# battery_board.net
KiCad netlist of a schematic drawn in EAGLE
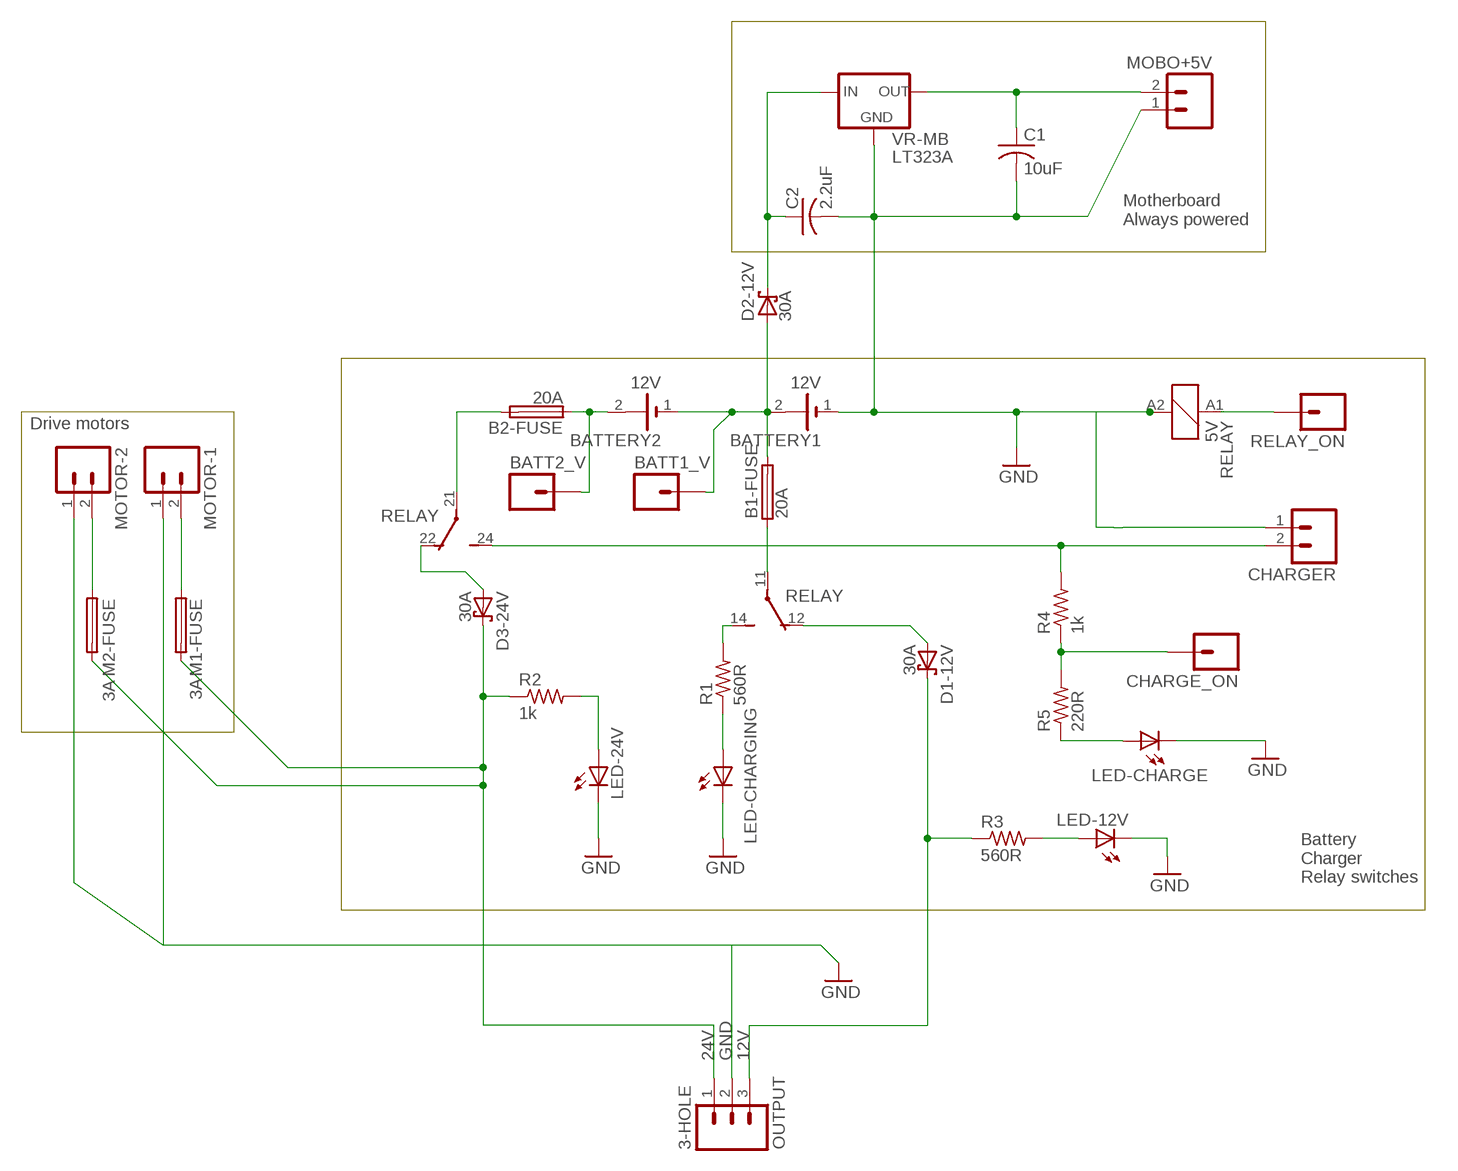
[diagram p0: schematic, sheet 1]

(export (version "E")
  (design (tool "Eeschema 10.0.6"))
  (components
    (comp (ref "B1-FUSE")
      (value "20A")
      (footprint "eagle-import:FUSE_BLADE")
      (libsource (lib "eagle-import") (part "FUSEBLADE"))
    )
    (comp (ref "B2-FUSE")
      (value "20A")
      (footprint "eagle-import:FUSE_BLADE")
      (libsource (lib "eagle-import") (part "FUSEBLADE"))
    )
    (comp (ref "BATT1_V")
      (value "1-HOLE")
      (footprint "eagle-import:1-HOLE_BIG")
      (libsource (lib "eagle-import") (part "1-HOLE"))
    )
    (comp (ref "BATT2_V")
      (value "1-HOLE")
      (footprint "eagle-import:1-HOLE_BIG")
      (libsource (lib "eagle-import") (part "1-HOLE"))
    )
    (comp (ref "BATTERY1")
      (value "12V")
      (footprint "eagle-import:SCREWTERMINAL-5MM-2")
      (libsource (lib "eagle-import") (part "BATTERY-ST"))
    )
    (comp (ref "BATTERY2")
      (value "12V")
      (footprint "eagle-import:SCREWTERMINAL-5MM-2")
      (libsource (lib "eagle-import") (part "BATTERY-ST"))
    )
    (comp (ref "C1")
      (value "10uF")
      (footprint "eagle-import:C050-024X044")
      (libsource (lib "eagle-import") (part "CAPACITOR"))
    )
    (comp (ref "C2")
      (value "2.2uF")
      (footprint "eagle-import:C050-024X044")
      (libsource (lib "eagle-import") (part "CAPACITOR"))
    )
    (comp (ref "CHARGER")
      (value "24V")
      (footprint "eagle-import:SCREWTERMINAL-5MM-2")
      (libsource (lib "eagle-import") (part "2-HOLESSC5MM"))
    )
    (comp (ref "CHARGE_ON")
      (value "1-HOLE")
      (footprint "eagle-import:1-HOLE_BIG")
      (libsource (lib "eagle-import") (part "1-HOLE"))
    )
    (comp (ref "D1-12V")
      (value "30A")
      (footprint "eagle-import:TO22-DIODE-H")
      (libsource (lib "eagle-import") (part "NTST30100SG-H"))
    )
    (comp (ref "D2-12V")
      (value "30A")
      (footprint "eagle-import:TO22-DIODE-H")
      (libsource (lib "eagle-import") (part "NTST30100SG-H"))
    )
    (comp (ref "D3-24V")
      (value "30A")
      (footprint "eagle-import:TO22-DIODE-H")
      (libsource (lib "eagle-import") (part "NTST30100SG-H"))
    )
    (comp (ref "LED-12V")
      (value "LED-5MM")
      (footprint "eagle-import:LED5MM")
      (libsource (lib "eagle-import") (part "LED-5MM"))
    )
    (comp (ref "LED-24V")
      (value "LED-5MM")
      (footprint "eagle-import:LED5MM")
      (libsource (lib "eagle-import") (part "LED-5MM"))
    )
    (comp (ref "LED-CHARGE")
      (value "LED-5MM")
      (footprint "eagle-import:LED5MM")
      (libsource (lib "eagle-import") (part "LED-5MM"))
    )
    (comp (ref "LED-CHARGING")
      (value "LED-5MM")
      (footprint "eagle-import:LED5MM")
      (libsource (lib "eagle-import") (part "LED-5MM"))
    )
    (comp (ref "M1-FUSE")
      (value "3A")
      (footprint "eagle-import:FUSE-5X20MM_SMD")
      (libsource (lib "eagle-import") (part "FUSE"))
    )
    (comp (ref "M2-FUSE")
      (value "3A")
      (footprint "eagle-import:FUSE-5X20MM_SMD")
      (libsource (lib "eagle-import") (part "FUSE"))
    )
    (comp (ref "MOBO+5V")
      (value "2-HOLESSC3.81MM")
      (footprint "eagle-import:SCREWTERMINAL-3.81MM")
      (libsource (lib "eagle-import") (part "2-HOLESSC3.81MM"))
    )
    (comp (ref "MOTOR-1")
      (value "2-HOLESSC5MM")
      (footprint "eagle-import:SCREWTERMINAL-5MM-2")
      (libsource (lib "eagle-import") (part "2-HOLESSC5MM"))
    )
    (comp (ref "MOTOR-2")
      (value "2-HOLESSC5MM")
      (footprint "eagle-import:SCREWTERMINAL-5MM-2")
      (libsource (lib "eagle-import") (part "2-HOLESSC5MM"))
    )
    (comp (ref "OUTPUT")
      (value "3-HOLE")
      (footprint "eagle-import:SCREWTERMINAL-5MM-3")
      (libsource (lib "eagle-import") (part "3-HOLE"))
    )
    (comp (ref "R1")
      (value "560R")
      (footprint "eagle-import:0207_10")
      (libsource (lib "eagle-import") (part "RESISTOR0207/10"))
    )
    (comp (ref "R2")
      (value "1k")
      (footprint "eagle-import:0207_10")
      (libsource (lib "eagle-import") (part "RESISTOR0207/10"))
    )
    (comp (ref "R3")
      (value "560R")
      (footprint "eagle-import:0207_10")
      (libsource (lib "eagle-import") (part "RESISTOR0207/10"))
    )
    (comp (ref "R4")
      (value "1k")
      (footprint "eagle-import:0207_10")
      (libsource (lib "eagle-import") (part "RESISTOR0207/10"))
    )
    (comp (ref "R5")
      (value "220R")
      (footprint "eagle-import:0207_10")
      (libsource (lib "eagle-import") (part "RESISTOR0207/10"))
    )
    (comp (ref "RELAY")
      (value "5V")
      (footprint "eagle-import:RELAY_RT2")
      (fields (field (name "MPN") "RT424A05"))
      (libsource (lib "eagle-import") (part "RT424A05"))
    )
    (comp (ref "RELAY_ON")
      (value "1-HOLE\"")
      (footprint "eagle-import:1-HOLE")
      (libsource (lib "eagle-import") (part "1-HOLE{dblquote}"))
    )
    (comp (ref "VR-MB")
      (value "LT323A")
      (footprint "eagle-import:TO220V-HEATSINK")
      (libsource (lib "eagle-import") (part "LT323AT-SINK"))
    )
  )
  (nets
    (net (code "1") (name "/12V") (class "Default")
      (node (ref "D1-12V") (pin "P$2") (pinfunction "C_P$2") (pintype "passive"))
      (node (ref "OUTPUT") (pin "3") (pinfunction "3_3") (pintype "passive"))
      (node (ref "R3") (pin "1") (pinfunction "1_1") (pintype "passive"))
    )
    (net (code "2") (name "/24V") (class "Default")
      (node (ref "D3-24V") (pin "P$2") (pinfunction "C_P$2") (pintype "passive"))
      (node (ref "M1-FUSE") (pin "P$2") (pinfunction "2_P$2") (pintype "passive"))
      (node (ref "M2-FUSE") (pin "P$2") (pinfunction "2_P$2") (pintype "passive"))
      (node (ref "OUTPUT") (pin "1") (pinfunction "1_1") (pintype "passive"))
      (node (ref "R2") (pin "1") (pinfunction "1_1") (pintype "passive"))
    )
    (net (code "3") (name "GND") (class "Default")
      (node (ref "BATTERY1") (pin "1") (pinfunction "-_1") (pintype "passive"))
      (node (ref "C1") (pin "2") (pinfunction "2_2") (pintype "passive"))
      (node (ref "C2") (pin "2") (pinfunction "2_2") (pintype "passive"))
      (node (ref "CHARGER") (pin "1") (pinfunction "1_1") (pintype "passive"))
      (node (ref "LED-12V") (pin "K") (pinfunction "C_K") (pintype "passive"))
      (node (ref "LED-24V") (pin "K") (pinfunction "C_K") (pintype "passive"))
      (node (ref "LED-CHARGE") (pin "K") (pinfunction "C_K") (pintype "passive"))
      (node (ref "LED-CHARGING") (pin "K") (pinfunction "C_K") (pintype "passive"))
      (node (ref "MOBO+5V") (pin "1") (pinfunction "1_1") (pintype "passive"))
      (node (ref "MOTOR-1") (pin "1") (pinfunction "1_1") (pintype "passive"))
      (node (ref "MOTOR-2") (pin "1") (pinfunction "1_1") (pintype "passive"))
      (node (ref "OUTPUT") (pin "2") (pinfunction "2_2") (pintype "passive"))
      (node (ref "RELAY") (pin "A2") (pinfunction "2_A2") (pintype "passive"))
      (node (ref "VR-MB") (pin "2") (pinfunction "GND_2") (pintype "input"))
    )
    (net (code "4") (name "Net-(B1-FUSE-1)") (class "Default")
      (node (ref "B1-FUSE") (pin "P$1") (pinfunction "1_P$1") (pintype "passive"))
      (node (ref "RELAY") (pin "11") (pinfunction "P_11") (pintype "passive"))
    )
    (net (code "5") (name "Net-(B1-FUSE-2)") (class "Default")
      (node (ref "B1-FUSE") (pin "P$2") (pinfunction "2_P$2") (pintype "passive"))
      (node (ref "BATT1_V") (pin "P$1") (pinfunction "1_P$1") (pintype "passive"))
      (node (ref "BATTERY1") (pin "2") (pinfunction "+_2") (pintype "passive"))
      (node (ref "BATTERY2") (pin "1") (pinfunction "-_1") (pintype "passive"))
      (node (ref "D2-12V") (pin "P$1") (pinfunction "A_P$1") (pintype "passive"))
    )
    (net (code "6") (name "Net-(B2-FUSE-1)") (class "Default")
      (node (ref "B2-FUSE") (pin "P$1") (pinfunction "1_P$1") (pintype "passive"))
      (node (ref "BATT2_V") (pin "P$1") (pinfunction "1_P$1") (pintype "passive"))
      (node (ref "BATTERY2") (pin "2") (pinfunction "+_2") (pintype "passive"))
    )
    (net (code "7") (name "Net-(B2-FUSE-2)") (class "Default")
      (node (ref "B2-FUSE") (pin "P$2") (pinfunction "2_P$2") (pintype "passive"))
      (node (ref "RELAY") (pin "21") (pinfunction "P_21") (pintype "passive"))
    )
    (net (code "8") (name "Net-(CHARGE_ON-1)") (class "Default")
      (node (ref "CHARGE_ON") (pin "P$1") (pinfunction "1_P$1") (pintype "passive"))
      (node (ref "R4") (pin "1") (pinfunction "1_1") (pintype "passive"))
      (node (ref "R5") (pin "2") (pinfunction "2_2") (pintype "passive"))
    )
    (net (code "9") (name "Net-(D1-12V-A)") (class "Default")
      (node (ref "D1-12V") (pin "P$1") (pinfunction "A_P$1") (pintype "passive"))
      (node (ref "RELAY") (pin "12") (pinfunction "O_12") (pintype "passive"))
    )
    (net (code "10") (name "Net-(D2-12V-C)") (class "Default")
      (node (ref "C2") (pin "1") (pinfunction "1_1") (pintype "passive"))
      (node (ref "D2-12V") (pin "P$2") (pinfunction "C_P$2") (pintype "passive"))
      (node (ref "VR-MB") (pin "1") (pinfunction "IN_1") (pintype "input"))
    )
    (net (code "11") (name "Net-(D3-24V-A)") (class "Default")
      (node (ref "D3-24V") (pin "P$1") (pinfunction "A_P$1") (pintype "passive"))
      (node (ref "RELAY") (pin "22") (pinfunction "O_22") (pintype "passive"))
    )
    (net (code "12") (name "Net-(LED-12V-PadA)") (class "Default")
      (node (ref "LED-12V") (pin "A") (pinfunction "A_A") (pintype "passive"))
      (node (ref "R3") (pin "2") (pinfunction "2_2") (pintype "passive"))
    )
    (net (code "13") (name "Net-(LED-24V-PadA)") (class "Default")
      (node (ref "LED-24V") (pin "A") (pinfunction "A_A") (pintype "passive"))
      (node (ref "R2") (pin "2") (pinfunction "2_2") (pintype "passive"))
    )
    (net (code "14") (name "Net-(LED-CHARGE-PadA)") (class "Default")
      (node (ref "LED-CHARGE") (pin "A") (pinfunction "A_A") (pintype "passive"))
      (node (ref "R5") (pin "1") (pinfunction "1_1") (pintype "passive"))
    )
    (net (code "15") (name "Net-(LED-CHARGING-PadA)") (class "Default")
      (node (ref "LED-CHARGING") (pin "A") (pinfunction "A_A") (pintype "passive"))
      (node (ref "R1") (pin "1") (pinfunction "1_1") (pintype "passive"))
    )
    (net (code "16") (name "Net-(M1-FUSE-1)") (class "Default")
      (node (ref "M1-FUSE") (pin "P$1") (pinfunction "1_P$1") (pintype "passive"))
      (node (ref "MOTOR-1") (pin "2") (pinfunction "2_2") (pintype "passive"))
    )
    (net (code "17") (name "Net-(M2-FUSE-1)") (class "Default")
      (node (ref "M2-FUSE") (pin "P$1") (pinfunction "1_P$1") (pintype "passive"))
      (node (ref "MOTOR-2") (pin "2") (pinfunction "2_2") (pintype "passive"))
    )
    (net (code "18") (name "Net-(RELAYA-1)") (class "Default")
      (node (ref "RELAY") (pin "A1") (pinfunction "1_A1") (pintype "passive"))
      (node (ref "RELAY_ON") (pin "1") (pinfunction "1_1") (pintype "passive"))
    )
    (net (code "19") (name "Net-(RELAYB-S)") (class "Default")
      (node (ref "R1") (pin "2") (pinfunction "2_2") (pintype "passive"))
      (node (ref "RELAY") (pin "14") (pinfunction "S_14") (pintype "passive"))
    )
    (net (code "20") (name "Net-(RELAYC-S)") (class "Default")
      (node (ref "CHARGER") (pin "2") (pinfunction "2_2") (pintype "passive"))
      (node (ref "R4") (pin "2") (pinfunction "2_2") (pintype "passive"))
      (node (ref "RELAY") (pin "24") (pinfunction "S_24") (pintype "passive"))
    )
    (net (code "21") (name "Net-(VR-MB-OUT)") (class "Default")
      (node (ref "C1") (pin "1") (pinfunction "1_1") (pintype "passive"))
      (node (ref "MOBO+5V") (pin "2") (pinfunction "2_2") (pintype "passive"))
      (node (ref "VR-MB") (pin "3") (pinfunction "OUT_3") (pintype "passive"))
    )
  )
)
